# L-Stick_sheet4_leds.net
KiCad netlist of a schematic drawn in Altium Designer
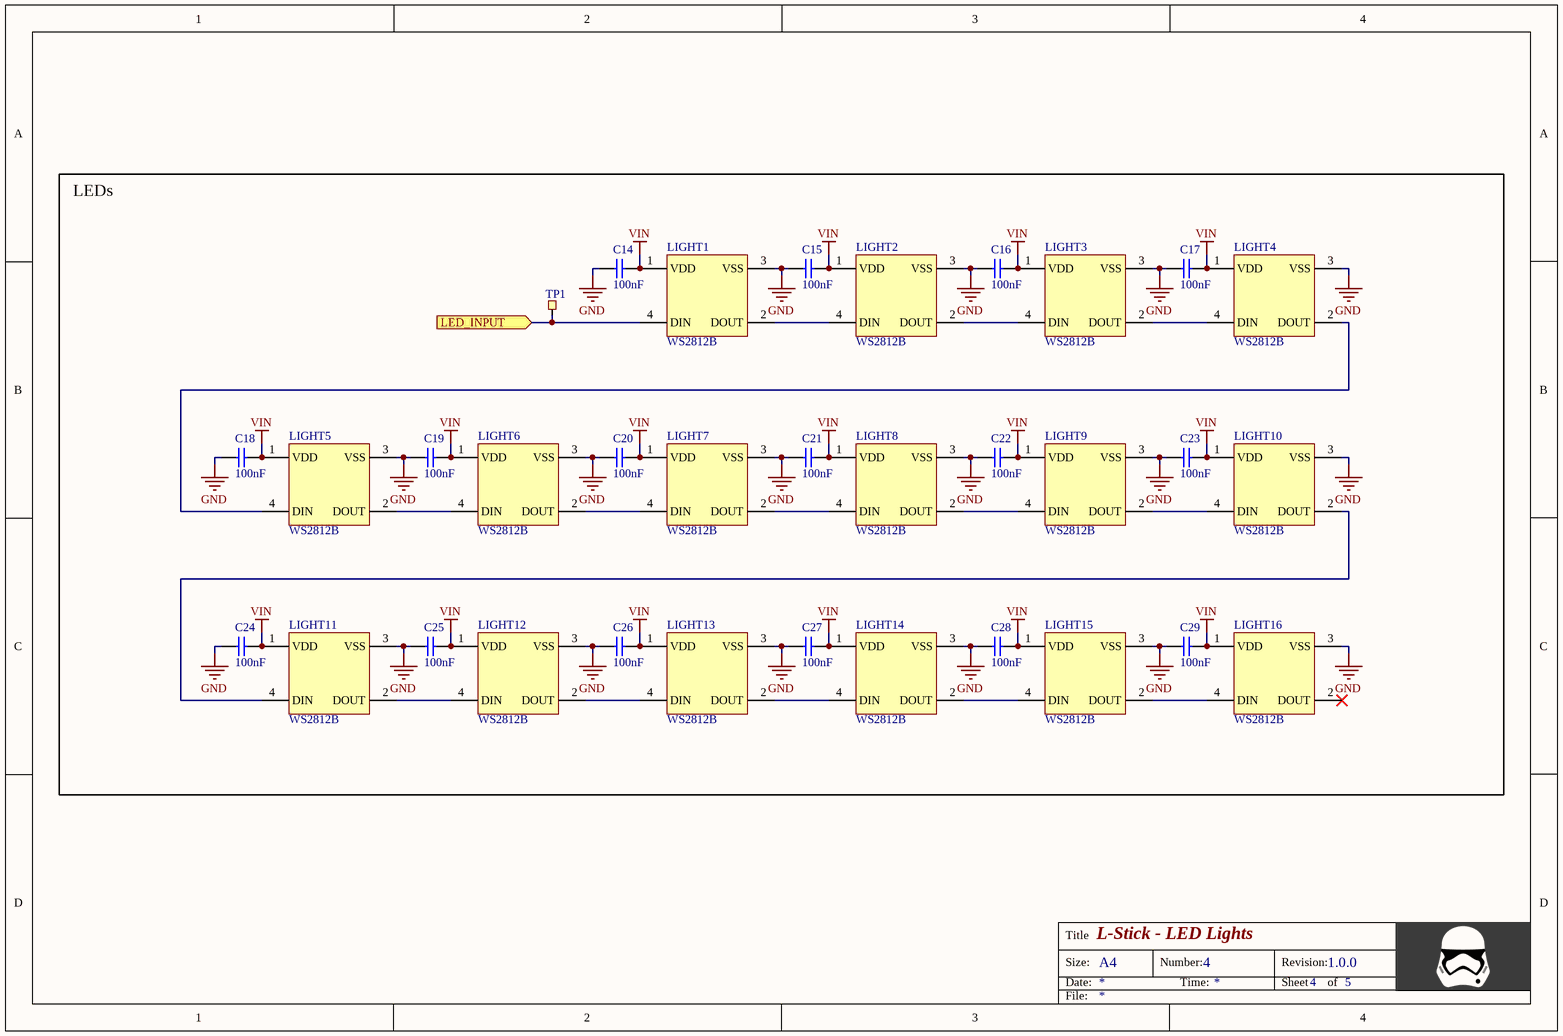
[diagram p0: L-Stick_sheet4_leds.SchDoc]

(export (version "E")
  (design (tool "Eeschema 10.0.6"))
  (components
    (comp (ref "C14")
      (value "100nF")
      (footprint "0402C")
      (description "Capacitor")
      (libsource (lib "L-Stick") (part "CAP_0402"))
    )
    (comp (ref "C15")
      (value "100nF")
      (footprint "0402C")
      (description "Capacitor")
      (libsource (lib "L-Stick") (part "CAP_0402"))
    )
    (comp (ref "C16")
      (value "100nF")
      (footprint "0402C")
      (description "Capacitor")
      (libsource (lib "L-Stick") (part "CAP_0402"))
    )
    (comp (ref "C17")
      (value "100nF")
      (footprint "0402C")
      (description "Capacitor")
      (libsource (lib "L-Stick") (part "CAP_0402"))
    )
    (comp (ref "C18")
      (value "100nF")
      (footprint "0402C")
      (description "Capacitor")
      (libsource (lib "L-Stick") (part "CAP_0402"))
    )
    (comp (ref "C19")
      (value "100nF")
      (footprint "0402C")
      (description "Capacitor")
      (libsource (lib "L-Stick") (part "CAP_0402"))
    )
    (comp (ref "C20")
      (value "100nF")
      (footprint "0402C")
      (description "Capacitor")
      (libsource (lib "L-Stick") (part "CAP_0402"))
    )
    (comp (ref "C21")
      (value "100nF")
      (footprint "0402C")
      (description "Capacitor")
      (libsource (lib "L-Stick") (part "CAP_0402"))
    )
    (comp (ref "C22")
      (value "100nF")
      (footprint "0402C")
      (description "Capacitor")
      (libsource (lib "L-Stick") (part "CAP_0402"))
    )
    (comp (ref "C23")
      (value "100nF")
      (footprint "0402C")
      (description "Capacitor")
      (libsource (lib "L-Stick") (part "CAP_0402"))
    )
    (comp (ref "C24")
      (value "100nF")
      (footprint "0402C")
      (description "Capacitor")
      (libsource (lib "L-Stick") (part "CAP_0402"))
    )
    (comp (ref "C25")
      (value "100nF")
      (footprint "0402C")
      (description "Capacitor")
      (libsource (lib "L-Stick") (part "CAP_0402"))
    )
    (comp (ref "C26")
      (value "100nF")
      (footprint "0402C")
      (description "Capacitor")
      (libsource (lib "L-Stick") (part "CAP_0402"))
    )
    (comp (ref "C27")
      (value "100nF")
      (footprint "0402C")
      (description "Capacitor")
      (libsource (lib "L-Stick") (part "CAP_0402"))
    )
    (comp (ref "C28")
      (value "100nF")
      (footprint "0402C")
      (description "Capacitor")
      (libsource (lib "L-Stick") (part "CAP_0402"))
    )
    (comp (ref "C29")
      (value "100nF")
      (footprint "0402C")
      (description "Capacitor")
      (libsource (lib "L-Stick") (part "CAP_0402"))
    )
    (comp (ref "LIGHT1")
      (value "WS2812B")
      (footprint "WS2812B")
      (description "Integrated RGB LED")
      (libsource (lib "L-Stick") (part "WS2812B"))
    )
    (comp (ref "LIGHT2")
      (value "WS2812B")
      (footprint "WS2812B")
      (description "Integrated RGB LED")
      (libsource (lib "L-Stick") (part "WS2812B"))
    )
    (comp (ref "LIGHT3")
      (value "WS2812B")
      (footprint "WS2812B")
      (description "Integrated RGB LED")
      (libsource (lib "L-Stick") (part "WS2812B"))
    )
    (comp (ref "LIGHT4")
      (value "WS2812B")
      (footprint "WS2812B")
      (description "Integrated RGB LED")
      (libsource (lib "L-Stick") (part "WS2812B"))
    )
    (comp (ref "LIGHT5")
      (value "WS2812B")
      (footprint "WS2812B")
      (description "Integrated RGB LED")
      (libsource (lib "L-Stick") (part "WS2812B"))
    )
    (comp (ref "LIGHT6")
      (value "WS2812B")
      (footprint "WS2812B")
      (description "Integrated RGB LED")
      (libsource (lib "L-Stick") (part "WS2812B"))
    )
    (comp (ref "LIGHT7")
      (value "WS2812B")
      (footprint "WS2812B")
      (description "Integrated RGB LED")
      (libsource (lib "L-Stick") (part "WS2812B"))
    )
    (comp (ref "LIGHT8")
      (value "WS2812B")
      (footprint "WS2812B")
      (description "Integrated RGB LED")
      (libsource (lib "L-Stick") (part "WS2812B"))
    )
    (comp (ref "LIGHT9")
      (value "WS2812B")
      (footprint "WS2812B")
      (description "Integrated RGB LED")
      (libsource (lib "L-Stick") (part "WS2812B"))
    )
    (comp (ref "LIGHT10")
      (value "WS2812B")
      (footprint "WS2812B")
      (description "Integrated RGB LED")
      (libsource (lib "L-Stick") (part "WS2812B"))
    )
    (comp (ref "LIGHT11")
      (value "WS2812B")
      (footprint "WS2812B")
      (description "Integrated RGB LED")
      (libsource (lib "L-Stick") (part "WS2812B"))
    )
    (comp (ref "LIGHT12")
      (value "WS2812B")
      (footprint "WS2812B")
      (description "Integrated RGB LED")
      (libsource (lib "L-Stick") (part "WS2812B"))
    )
    (comp (ref "LIGHT13")
      (value "WS2812B")
      (footprint "WS2812B")
      (description "Integrated RGB LED")
      (libsource (lib "L-Stick") (part "WS2812B"))
    )
    (comp (ref "LIGHT14")
      (value "WS2812B")
      (footprint "WS2812B")
      (description "Integrated RGB LED")
      (libsource (lib "L-Stick") (part "WS2812B"))
    )
    (comp (ref "LIGHT15")
      (value "WS2812B")
      (footprint "WS2812B")
      (description "Integrated RGB LED")
      (libsource (lib "L-Stick") (part "WS2812B"))
    )
    (comp (ref "LIGHT16")
      (value "WS2812B")
      (footprint "WS2812B")
      (description "Integrated RGB LED")
      (libsource (lib "L-Stick") (part "WS2812B"))
    )
    (comp (ref "TP1")
      (value "Ø1.5mm,SMD")
      (footprint "TP_SMD")
      (description "1.0mm circular SMD testpad")
      (libsource (lib "L-Stick") (part "TP_SMD_Ø1.0MM"))
    )
  )
  (nets
    (net (code "1") (name "/LED_INPUT") (class "Default")
      (node (ref "LIGHT1") (pin "4") (pinfunction "DIN_4") (pintype "passive"))
      (node (ref "TP1") (pin "1") (pinfunction "1_1") (pintype "passive"))
    )
    (net (code "2") (name "GND") (class "Default")
      (node (ref "C14") (pin "1") (pinfunction "1_1") (pintype "passive"))
      (node (ref "C15") (pin "1") (pinfunction "1_1") (pintype "passive"))
      (node (ref "C16") (pin "1") (pinfunction "1_1") (pintype "passive"))
      (node (ref "C17") (pin "1") (pinfunction "1_1") (pintype "passive"))
      (node (ref "C18") (pin "1") (pinfunction "1_1") (pintype "passive"))
      (node (ref "C19") (pin "1") (pinfunction "1_1") (pintype "passive"))
      (node (ref "C20") (pin "1") (pinfunction "1_1") (pintype "passive"))
      (node (ref "C21") (pin "1") (pinfunction "1_1") (pintype "passive"))
      (node (ref "C22") (pin "1") (pinfunction "1_1") (pintype "passive"))
      (node (ref "C23") (pin "1") (pinfunction "1_1") (pintype "passive"))
      (node (ref "C24") (pin "1") (pinfunction "1_1") (pintype "passive"))
      (node (ref "C25") (pin "1") (pinfunction "1_1") (pintype "passive"))
      (node (ref "C26") (pin "1") (pinfunction "1_1") (pintype "passive"))
      (node (ref "C27") (pin "1") (pinfunction "1_1") (pintype "passive"))
      (node (ref "C28") (pin "1") (pinfunction "1_1") (pintype "passive"))
      (node (ref "C29") (pin "1") (pinfunction "1_1") (pintype "passive"))
      (node (ref "LIGHT1") (pin "3") (pinfunction "VSS_3") (pintype "passive"))
      (node (ref "LIGHT10") (pin "3") (pinfunction "VSS_3") (pintype "passive"))
      (node (ref "LIGHT11") (pin "3") (pinfunction "VSS_3") (pintype "passive"))
      (node (ref "LIGHT12") (pin "3") (pinfunction "VSS_3") (pintype "passive"))
      (node (ref "LIGHT13") (pin "3") (pinfunction "VSS_3") (pintype "passive"))
      (node (ref "LIGHT14") (pin "3") (pinfunction "VSS_3") (pintype "passive"))
      (node (ref "LIGHT15") (pin "3") (pinfunction "VSS_3") (pintype "passive"))
      (node (ref "LIGHT16") (pin "3") (pinfunction "VSS_3") (pintype "passive"))
      (node (ref "LIGHT2") (pin "3") (pinfunction "VSS_3") (pintype "passive"))
      (node (ref "LIGHT3") (pin "3") (pinfunction "VSS_3") (pintype "passive"))
      (node (ref "LIGHT4") (pin "3") (pinfunction "VSS_3") (pintype "passive"))
      (node (ref "LIGHT5") (pin "3") (pinfunction "VSS_3") (pintype "passive"))
      (node (ref "LIGHT6") (pin "3") (pinfunction "VSS_3") (pintype "passive"))
      (node (ref "LIGHT7") (pin "3") (pinfunction "VSS_3") (pintype "passive"))
      (node (ref "LIGHT8") (pin "3") (pinfunction "VSS_3") (pintype "passive"))
      (node (ref "LIGHT9") (pin "3") (pinfunction "VSS_3") (pintype "passive"))
    )
    (net (code "3") (name "Net-(LIGHT1-DOUT)") (class "Default")
      (node (ref "LIGHT1") (pin "2") (pinfunction "DOUT_2") (pintype "passive"))
      (node (ref "LIGHT2") (pin "4") (pinfunction "DIN_4") (pintype "passive"))
    )
    (net (code "4") (name "Net-(LIGHT2-DOUT)") (class "Default")
      (node (ref "LIGHT2") (pin "2") (pinfunction "DOUT_2") (pintype "passive"))
      (node (ref "LIGHT3") (pin "4") (pinfunction "DIN_4") (pintype "passive"))
    )
    (net (code "5") (name "Net-(LIGHT3-DOUT)") (class "Default")
      (node (ref "LIGHT3") (pin "2") (pinfunction "DOUT_2") (pintype "passive"))
      (node (ref "LIGHT4") (pin "4") (pinfunction "DIN_4") (pintype "passive"))
    )
    (net (code "6") (name "Net-(LIGHT4-DOUT)") (class "Default")
      (node (ref "LIGHT4") (pin "2") (pinfunction "DOUT_2") (pintype "passive"))
      (node (ref "LIGHT5") (pin "4") (pinfunction "DIN_4") (pintype "passive"))
    )
    (net (code "7") (name "Net-(LIGHT5-DOUT)") (class "Default")
      (node (ref "LIGHT5") (pin "2") (pinfunction "DOUT_2") (pintype "passive"))
      (node (ref "LIGHT6") (pin "4") (pinfunction "DIN_4") (pintype "passive"))
    )
    (net (code "8") (name "Net-(LIGHT6-DOUT)") (class "Default")
      (node (ref "LIGHT6") (pin "2") (pinfunction "DOUT_2") (pintype "passive"))
      (node (ref "LIGHT7") (pin "4") (pinfunction "DIN_4") (pintype "passive"))
    )
    (net (code "9") (name "Net-(LIGHT7-DOUT)") (class "Default")
      (node (ref "LIGHT7") (pin "2") (pinfunction "DOUT_2") (pintype "passive"))
      (node (ref "LIGHT8") (pin "4") (pinfunction "DIN_4") (pintype "passive"))
    )
    (net (code "10") (name "Net-(LIGHT8-DOUT)") (class "Default")
      (node (ref "LIGHT8") (pin "2") (pinfunction "DOUT_2") (pintype "passive"))
      (node (ref "LIGHT9") (pin "4") (pinfunction "DIN_4") (pintype "passive"))
    )
    (net (code "11") (name "Net-(LIGHT10-DIN)") (class "Default")
      (node (ref "LIGHT10") (pin "4") (pinfunction "DIN_4") (pintype "passive"))
      (node (ref "LIGHT9") (pin "2") (pinfunction "DOUT_2") (pintype "passive"))
    )
    (net (code "12") (name "Net-(LIGHT10-DOUT)") (class "Default")
      (node (ref "LIGHT10") (pin "2") (pinfunction "DOUT_2") (pintype "passive"))
      (node (ref "LIGHT11") (pin "4") (pinfunction "DIN_4") (pintype "passive"))
    )
    (net (code "13") (name "Net-(LIGHT11-DOUT)") (class "Default")
      (node (ref "LIGHT11") (pin "2") (pinfunction "DOUT_2") (pintype "passive"))
      (node (ref "LIGHT12") (pin "4") (pinfunction "DIN_4") (pintype "passive"))
    )
    (net (code "14") (name "Net-(LIGHT12-DOUT)") (class "Default")
      (node (ref "LIGHT12") (pin "2") (pinfunction "DOUT_2") (pintype "passive"))
      (node (ref "LIGHT13") (pin "4") (pinfunction "DIN_4") (pintype "passive"))
    )
    (net (code "15") (name "Net-(LIGHT13-DOUT)") (class "Default")
      (node (ref "LIGHT13") (pin "2") (pinfunction "DOUT_2") (pintype "passive"))
      (node (ref "LIGHT14") (pin "4") (pinfunction "DIN_4") (pintype "passive"))
    )
    (net (code "16") (name "Net-(LIGHT14-DOUT)") (class "Default")
      (node (ref "LIGHT14") (pin "2") (pinfunction "DOUT_2") (pintype "passive"))
      (node (ref "LIGHT15") (pin "4") (pinfunction "DIN_4") (pintype "passive"))
    )
    (net (code "17") (name "Net-(LIGHT15-DOUT)") (class "Default")
      (node (ref "LIGHT15") (pin "2") (pinfunction "DOUT_2") (pintype "passive"))
      (node (ref "LIGHT16") (pin "4") (pinfunction "DIN_4") (pintype "passive"))
    )
    (net (code "18") (name "VIN") (class "Default")
      (node (ref "C14") (pin "2") (pinfunction "2_2") (pintype "passive"))
      (node (ref "C15") (pin "2") (pinfunction "2_2") (pintype "passive"))
      (node (ref "C16") (pin "2") (pinfunction "2_2") (pintype "passive"))
      (node (ref "C17") (pin "2") (pinfunction "2_2") (pintype "passive"))
      (node (ref "C18") (pin "2") (pinfunction "2_2") (pintype "passive"))
      (node (ref "C19") (pin "2") (pinfunction "2_2") (pintype "passive"))
      (node (ref "C20") (pin "2") (pinfunction "2_2") (pintype "passive"))
      (node (ref "C21") (pin "2") (pinfunction "2_2") (pintype "passive"))
      (node (ref "C22") (pin "2") (pinfunction "2_2") (pintype "passive"))
      (node (ref "C23") (pin "2") (pinfunction "2_2") (pintype "passive"))
      (node (ref "C24") (pin "2") (pinfunction "2_2") (pintype "passive"))
      (node (ref "C25") (pin "2") (pinfunction "2_2") (pintype "passive"))
      (node (ref "C26") (pin "2") (pinfunction "2_2") (pintype "passive"))
      (node (ref "C27") (pin "2") (pinfunction "2_2") (pintype "passive"))
      (node (ref "C28") (pin "2") (pinfunction "2_2") (pintype "passive"))
      (node (ref "C29") (pin "2") (pinfunction "2_2") (pintype "passive"))
      (node (ref "LIGHT1") (pin "1") (pinfunction "VDD_1") (pintype "passive"))
      (node (ref "LIGHT10") (pin "1") (pinfunction "VDD_1") (pintype "passive"))
      (node (ref "LIGHT11") (pin "1") (pinfunction "VDD_1") (pintype "passive"))
      (node (ref "LIGHT12") (pin "1") (pinfunction "VDD_1") (pintype "passive"))
      (node (ref "LIGHT13") (pin "1") (pinfunction "VDD_1") (pintype "passive"))
      (node (ref "LIGHT14") (pin "1") (pinfunction "VDD_1") (pintype "passive"))
      (node (ref "LIGHT15") (pin "1") (pinfunction "VDD_1") (pintype "passive"))
      (node (ref "LIGHT16") (pin "1") (pinfunction "VDD_1") (pintype "passive"))
      (node (ref "LIGHT2") (pin "1") (pinfunction "VDD_1") (pintype "passive"))
      (node (ref "LIGHT3") (pin "1") (pinfunction "VDD_1") (pintype "passive"))
      (node (ref "LIGHT4") (pin "1") (pinfunction "VDD_1") (pintype "passive"))
      (node (ref "LIGHT5") (pin "1") (pinfunction "VDD_1") (pintype "passive"))
      (node (ref "LIGHT6") (pin "1") (pinfunction "VDD_1") (pintype "passive"))
      (node (ref "LIGHT7") (pin "1") (pinfunction "VDD_1") (pintype "passive"))
      (node (ref "LIGHT8") (pin "1") (pinfunction "VDD_1") (pintype "passive"))
      (node (ref "LIGHT9") (pin "1") (pinfunction "VDD_1") (pintype "passive"))
    )
    (net (code "19") (name "unconnected-(LIGHT16-DOUT-Pad2)") (class "Default")
      (node (ref "LIGHT16") (pin "2") (pinfunction "DOUT_2") (pintype "passive+no_connect"))
    )
  )
)
